# stm32f4-discovery-breakout-v2.net
KiCad netlist of a schematic drawn in EAGLE
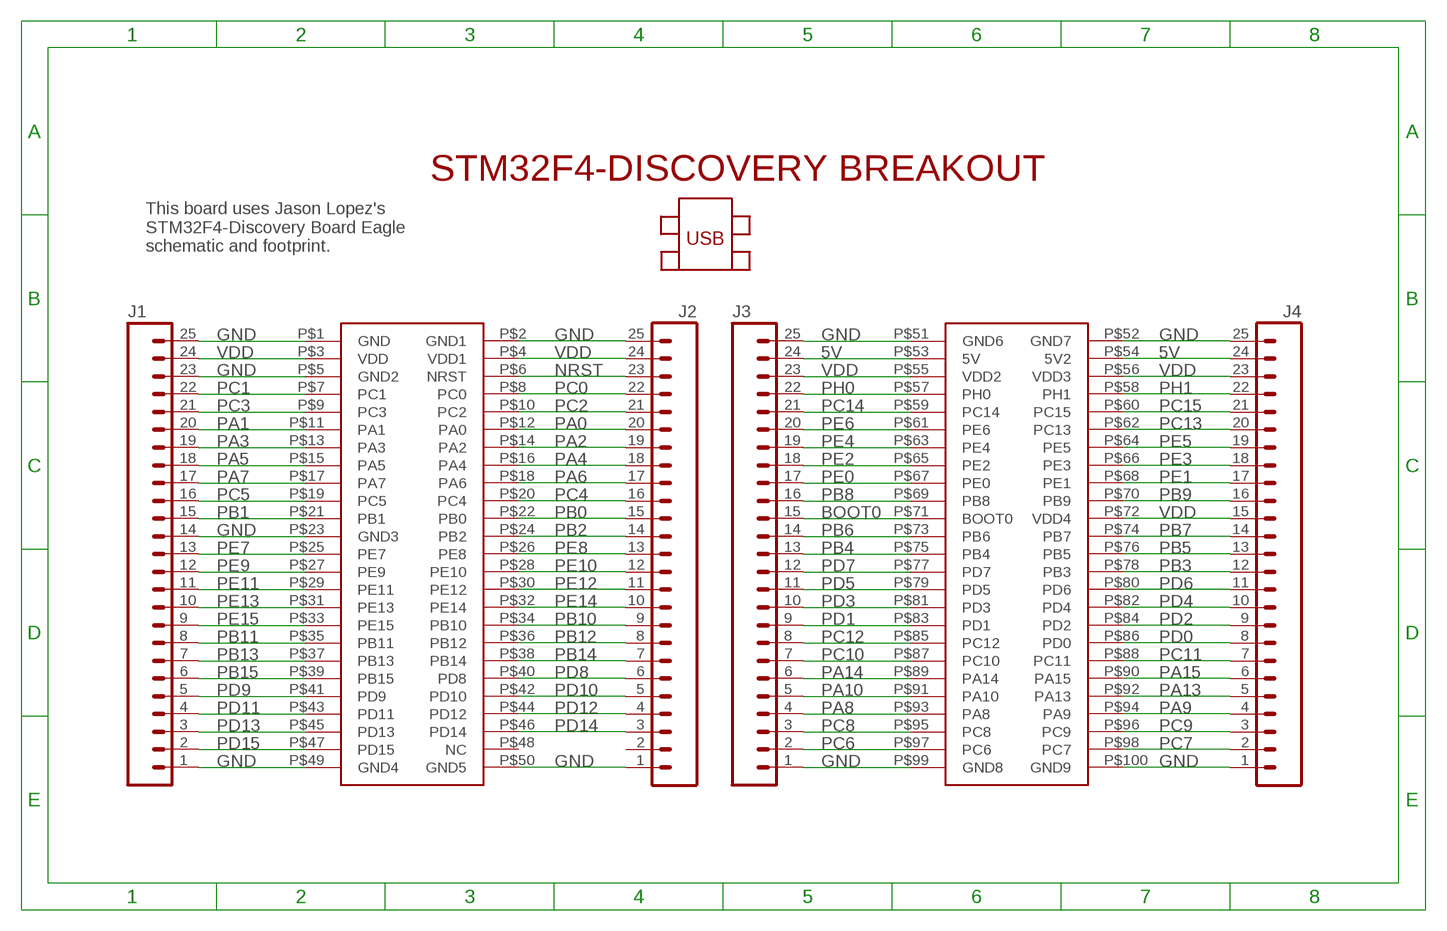
[diagram p0: schematic, sheet 1]

(export (version "E")
  (design (tool "Eeschema 10.0.6"))
  (components
    (comp (ref "J1")
      (value "M25LOCK_LONGPADS")
      (footprint "eagle-import:1X25_LOCK_LONGPADS")
      (libsource (lib "eagle-import") (part "M25LOCK_LONGPADS"))
    )
    (comp (ref "J2")
      (value "M25LOCK_LONGPADS")
      (footprint "eagle-import:1X25_LOCK_LONGPADS")
      (libsource (lib "eagle-import") (part "M25LOCK_LONGPADS"))
    )
    (comp (ref "J3")
      (value "M25LOCK_LONGPADS")
      (footprint "eagle-import:1X25_LOCK_LONGPADS")
      (libsource (lib "eagle-import") (part "M25LOCK_LONGPADS"))
    )
    (comp (ref "J4")
      (value "M25LOCK_LONGPADS")
      (footprint "eagle-import:1X25_LOCK_LONGPADS")
      (libsource (lib "eagle-import") (part "M25LOCK_LONGPADS"))
    )
    (comp (ref "U$1")
      (value "STM32F4-DISCOVERY")
      (footprint "eagle-import:STM32F4-DISCOVERY")
      (libsource (lib "eagle-import") (part "STM32F4-DISCOVERY"))
    )
  )
  (nets
    (net (code "1") (name "/5V") (class "Default")
      (node (ref "J3") (pin "24") (pinfunction "24_24") (pintype "passive"))
      (node (ref "J4") (pin "24") (pinfunction "24_24") (pintype "passive"))
      (node (ref "U$1") (pin "P$53") (pinfunction "5V_P$53") (pintype "bidirectional"))
      (node (ref "U$1") (pin "P$54") (pinfunction "5V2_P$54") (pintype "bidirectional"))
    )
    (net (code "2") (name "/BOOT0") (class "Default")
      (node (ref "J3") (pin "15") (pinfunction "15_15") (pintype "passive"))
      (node (ref "U$1") (pin "P$71") (pinfunction "BOOT0_P$71") (pintype "bidirectional"))
    )
    (net (code "3") (name "/GND") (class "Default")
      (node (ref "J1") (pin "1") (pinfunction "1_1") (pintype "passive"))
      (node (ref "J1") (pin "14") (pinfunction "14_14") (pintype "passive"))
      (node (ref "J1") (pin "23") (pinfunction "23_23") (pintype "passive"))
      (node (ref "J1") (pin "25") (pinfunction "25_25") (pintype "passive"))
      (node (ref "J2") (pin "1") (pinfunction "1_1") (pintype "passive"))
      (node (ref "J2") (pin "25") (pinfunction "25_25") (pintype "passive"))
      (node (ref "J3") (pin "1") (pinfunction "1_1") (pintype "passive"))
      (node (ref "J3") (pin "25") (pinfunction "25_25") (pintype "passive"))
      (node (ref "J4") (pin "1") (pinfunction "1_1") (pintype "passive"))
      (node (ref "J4") (pin "25") (pinfunction "25_25") (pintype "passive"))
      (node (ref "U$1") (pin "P$1") (pinfunction "GND_P$1") (pintype "bidirectional"))
      (node (ref "U$1") (pin "P$100") (pinfunction "GND9_P$100") (pintype "bidirectional"))
      (node (ref "U$1") (pin "P$2") (pinfunction "GND1_P$2") (pintype "bidirectional"))
      (node (ref "U$1") (pin "P$23") (pinfunction "GND3_P$23") (pintype "bidirectional"))
      (node (ref "U$1") (pin "P$49") (pinfunction "GND4_P$49") (pintype "bidirectional"))
      (node (ref "U$1") (pin "P$5") (pinfunction "GND2_P$5") (pintype "bidirectional"))
      (node (ref "U$1") (pin "P$50") (pinfunction "GND5_P$50") (pintype "bidirectional"))
      (node (ref "U$1") (pin "P$51") (pinfunction "GND6_P$51") (pintype "bidirectional"))
      (node (ref "U$1") (pin "P$52") (pinfunction "GND7_P$52") (pintype "bidirectional"))
      (node (ref "U$1") (pin "P$99") (pinfunction "GND8_P$99") (pintype "bidirectional"))
    )
    (net (code "4") (name "/NRST") (class "Default")
      (node (ref "J2") (pin "23") (pinfunction "23_23") (pintype "passive"))
      (node (ref "U$1") (pin "P$6") (pinfunction "NRST_P$6") (pintype "bidirectional"))
    )
    (net (code "5") (name "/PA0") (class "Default")
      (node (ref "J2") (pin "20") (pinfunction "20_20") (pintype "passive"))
      (node (ref "U$1") (pin "P$12") (pinfunction "PA0_P$12") (pintype "bidirectional"))
    )
    (net (code "6") (name "/PA1") (class "Default")
      (node (ref "J1") (pin "20") (pinfunction "20_20") (pintype "passive"))
      (node (ref "U$1") (pin "P$11") (pinfunction "PA1_P$11") (pintype "bidirectional"))
    )
    (net (code "7") (name "/PA2") (class "Default")
      (node (ref "J2") (pin "19") (pinfunction "19_19") (pintype "passive"))
      (node (ref "U$1") (pin "P$14") (pinfunction "PA2_P$14") (pintype "bidirectional"))
    )
    (net (code "8") (name "/PA3") (class "Default")
      (node (ref "J1") (pin "19") (pinfunction "19_19") (pintype "passive"))
      (node (ref "U$1") (pin "P$13") (pinfunction "PA3_P$13") (pintype "bidirectional"))
    )
    (net (code "9") (name "/PA4") (class "Default")
      (node (ref "J2") (pin "18") (pinfunction "18_18") (pintype "passive"))
      (node (ref "U$1") (pin "P$16") (pinfunction "PA4_P$16") (pintype "bidirectional"))
    )
    (net (code "10") (name "/PA5") (class "Default")
      (node (ref "J1") (pin "18") (pinfunction "18_18") (pintype "passive"))
      (node (ref "U$1") (pin "P$15") (pinfunction "PA5_P$15") (pintype "bidirectional"))
    )
    (net (code "11") (name "/PA6") (class "Default")
      (node (ref "J2") (pin "17") (pinfunction "17_17") (pintype "passive"))
      (node (ref "U$1") (pin "P$18") (pinfunction "PA6_P$18") (pintype "bidirectional"))
    )
    (net (code "12") (name "/PA7") (class "Default")
      (node (ref "J1") (pin "17") (pinfunction "17_17") (pintype "passive"))
      (node (ref "U$1") (pin "P$17") (pinfunction "PA7_P$17") (pintype "bidirectional"))
    )
    (net (code "13") (name "/PA8") (class "Default")
      (node (ref "J3") (pin "4") (pinfunction "4_4") (pintype "passive"))
      (node (ref "U$1") (pin "P$93") (pinfunction "PA8_P$93") (pintype "bidirectional"))
    )
    (net (code "14") (name "/PA9") (class "Default")
      (node (ref "J4") (pin "4") (pinfunction "4_4") (pintype "passive"))
      (node (ref "U$1") (pin "P$94") (pinfunction "PA9_P$94") (pintype "bidirectional"))
    )
    (net (code "15") (name "/PA10") (class "Default")
      (node (ref "J3") (pin "5") (pinfunction "5_5") (pintype "passive"))
      (node (ref "U$1") (pin "P$91") (pinfunction "PA10_P$91") (pintype "bidirectional"))
    )
    (net (code "16") (name "/PA13") (class "Default")
      (node (ref "J4") (pin "5") (pinfunction "5_5") (pintype "passive"))
      (node (ref "U$1") (pin "P$92") (pinfunction "PA13_P$92") (pintype "bidirectional"))
    )
    (net (code "17") (name "/PA14") (class "Default")
      (node (ref "J3") (pin "6") (pinfunction "6_6") (pintype "passive"))
      (node (ref "U$1") (pin "P$89") (pinfunction "PA14_P$89") (pintype "bidirectional"))
    )
    (net (code "18") (name "/PA15") (class "Default")
      (node (ref "J4") (pin "6") (pinfunction "6_6") (pintype "passive"))
      (node (ref "U$1") (pin "P$90") (pinfunction "PA15_P$90") (pintype "bidirectional"))
    )
    (net (code "19") (name "/PB0") (class "Default")
      (node (ref "J2") (pin "15") (pinfunction "15_15") (pintype "passive"))
      (node (ref "U$1") (pin "P$22") (pinfunction "PB0_P$22") (pintype "bidirectional"))
    )
    (net (code "20") (name "/PB1") (class "Default")
      (node (ref "J1") (pin "15") (pinfunction "15_15") (pintype "passive"))
      (node (ref "U$1") (pin "P$21") (pinfunction "PB1_P$21") (pintype "bidirectional"))
    )
    (net (code "21") (name "/PB2") (class "Default")
      (node (ref "J2") (pin "14") (pinfunction "14_14") (pintype "passive"))
      (node (ref "U$1") (pin "P$24") (pinfunction "PB2_P$24") (pintype "bidirectional"))
    )
    (net (code "22") (name "/PB3") (class "Default")
      (node (ref "J4") (pin "12") (pinfunction "12_12") (pintype "passive"))
      (node (ref "U$1") (pin "P$78") (pinfunction "PB3_P$78") (pintype "bidirectional"))
    )
    (net (code "23") (name "/PB4") (class "Default")
      (node (ref "J3") (pin "13") (pinfunction "13_13") (pintype "passive"))
      (node (ref "U$1") (pin "P$75") (pinfunction "PB4_P$75") (pintype "bidirectional"))
    )
    (net (code "24") (name "/PB5") (class "Default")
      (node (ref "J4") (pin "13") (pinfunction "13_13") (pintype "passive"))
      (node (ref "U$1") (pin "P$76") (pinfunction "PB5_P$76") (pintype "bidirectional"))
    )
    (net (code "25") (name "/PB6") (class "Default")
      (node (ref "J3") (pin "14") (pinfunction "14_14") (pintype "passive"))
      (node (ref "U$1") (pin "P$73") (pinfunction "PB6_P$73") (pintype "bidirectional"))
    )
    (net (code "26") (name "/PB7") (class "Default")
      (node (ref "J4") (pin "14") (pinfunction "14_14") (pintype "passive"))
      (node (ref "U$1") (pin "P$74") (pinfunction "PB7_P$74") (pintype "bidirectional"))
    )
    (net (code "27") (name "/PB8") (class "Default")
      (node (ref "J3") (pin "16") (pinfunction "16_16") (pintype "passive"))
      (node (ref "U$1") (pin "P$69") (pinfunction "PB8_P$69") (pintype "bidirectional"))
    )
    (net (code "28") (name "/PB9") (class "Default")
      (node (ref "J4") (pin "16") (pinfunction "16_16") (pintype "passive"))
      (node (ref "U$1") (pin "P$70") (pinfunction "PB9_P$70") (pintype "bidirectional"))
    )
    (net (code "29") (name "/PB10") (class "Default")
      (node (ref "J2") (pin "9") (pinfunction "9_9") (pintype "passive"))
      (node (ref "U$1") (pin "P$34") (pinfunction "PB10_P$34") (pintype "bidirectional"))
    )
    (net (code "30") (name "/PB11") (class "Default")
      (node (ref "J1") (pin "8") (pinfunction "8_8") (pintype "passive"))
      (node (ref "U$1") (pin "P$35") (pinfunction "PB11_P$35") (pintype "bidirectional"))
    )
    (net (code "31") (name "/PB12") (class "Default")
      (node (ref "J2") (pin "8") (pinfunction "8_8") (pintype "passive"))
      (node (ref "U$1") (pin "P$36") (pinfunction "PB12_P$36") (pintype "bidirectional"))
    )
    (net (code "32") (name "/PB13") (class "Default")
      (node (ref "J1") (pin "7") (pinfunction "7_7") (pintype "passive"))
      (node (ref "U$1") (pin "P$37") (pinfunction "PB13_P$37") (pintype "bidirectional"))
    )
    (net (code "33") (name "/PB14") (class "Default")
      (node (ref "J2") (pin "7") (pinfunction "7_7") (pintype "passive"))
      (node (ref "U$1") (pin "P$38") (pinfunction "PB14_P$38") (pintype "bidirectional"))
    )
    (net (code "34") (name "/PB15") (class "Default")
      (node (ref "J1") (pin "6") (pinfunction "6_6") (pintype "passive"))
      (node (ref "U$1") (pin "P$39") (pinfunction "PB15_P$39") (pintype "bidirectional"))
    )
    (net (code "35") (name "/PC0") (class "Default")
      (node (ref "J2") (pin "22") (pinfunction "22_22") (pintype "passive"))
      (node (ref "U$1") (pin "P$8") (pinfunction "PC0_P$8") (pintype "bidirectional"))
    )
    (net (code "36") (name "/PC1") (class "Default")
      (node (ref "J1") (pin "22") (pinfunction "22_22") (pintype "passive"))
      (node (ref "U$1") (pin "P$7") (pinfunction "PC1_P$7") (pintype "bidirectional"))
    )
    (net (code "37") (name "/PC2") (class "Default")
      (node (ref "J2") (pin "21") (pinfunction "21_21") (pintype "passive"))
      (node (ref "U$1") (pin "P$10") (pinfunction "PC2_P$10") (pintype "bidirectional"))
    )
    (net (code "38") (name "/PC3") (class "Default")
      (node (ref "J1") (pin "21") (pinfunction "21_21") (pintype "passive"))
      (node (ref "U$1") (pin "P$9") (pinfunction "PC3_P$9") (pintype "bidirectional"))
    )
    (net (code "39") (name "/PC4") (class "Default")
      (node (ref "J2") (pin "16") (pinfunction "16_16") (pintype "passive"))
      (node (ref "U$1") (pin "P$20") (pinfunction "PC4_P$20") (pintype "bidirectional"))
    )
    (net (code "40") (name "/PC5") (class "Default")
      (node (ref "J1") (pin "16") (pinfunction "16_16") (pintype "passive"))
      (node (ref "U$1") (pin "P$19") (pinfunction "PC5_P$19") (pintype "bidirectional"))
    )
    (net (code "41") (name "/PC6") (class "Default")
      (node (ref "J3") (pin "2") (pinfunction "2_2") (pintype "passive"))
      (node (ref "U$1") (pin "P$97") (pinfunction "PC6_P$97") (pintype "bidirectional"))
    )
    (net (code "42") (name "/PC7") (class "Default")
      (node (ref "J4") (pin "2") (pinfunction "2_2") (pintype "passive"))
      (node (ref "U$1") (pin "P$98") (pinfunction "PC7_P$98") (pintype "bidirectional"))
    )
    (net (code "43") (name "/PC8") (class "Default")
      (node (ref "J3") (pin "3") (pinfunction "3_3") (pintype "passive"))
      (node (ref "U$1") (pin "P$95") (pinfunction "PC8_P$95") (pintype "bidirectional"))
    )
    (net (code "44") (name "/PC9") (class "Default")
      (node (ref "J4") (pin "3") (pinfunction "3_3") (pintype "passive"))
      (node (ref "U$1") (pin "P$96") (pinfunction "PC9_P$96") (pintype "bidirectional"))
    )
    (net (code "45") (name "/PC10") (class "Default")
      (node (ref "J3") (pin "7") (pinfunction "7_7") (pintype "passive"))
      (node (ref "U$1") (pin "P$87") (pinfunction "PC10_P$87") (pintype "bidirectional"))
    )
    (net (code "46") (name "/PC11") (class "Default")
      (node (ref "J4") (pin "7") (pinfunction "7_7") (pintype "passive"))
      (node (ref "U$1") (pin "P$88") (pinfunction "PC11_P$88") (pintype "bidirectional"))
    )
    (net (code "47") (name "/PC12") (class "Default")
      (node (ref "J3") (pin "8") (pinfunction "8_8") (pintype "passive"))
      (node (ref "U$1") (pin "P$85") (pinfunction "PC12_P$85") (pintype "bidirectional"))
    )
    (net (code "48") (name "/PC13") (class "Default")
      (node (ref "J4") (pin "20") (pinfunction "20_20") (pintype "passive"))
      (node (ref "U$1") (pin "P$62") (pinfunction "PC13_P$62") (pintype "bidirectional"))
    )
    (net (code "49") (name "/PC14") (class "Default")
      (node (ref "J3") (pin "21") (pinfunction "21_21") (pintype "passive"))
      (node (ref "U$1") (pin "P$59") (pinfunction "PC14_P$59") (pintype "bidirectional"))
    )
    (net (code "50") (name "/PC15") (class "Default")
      (node (ref "J4") (pin "21") (pinfunction "21_21") (pintype "passive"))
      (node (ref "U$1") (pin "P$60") (pinfunction "PC15_P$60") (pintype "bidirectional"))
    )
    (net (code "51") (name "/PD0") (class "Default")
      (node (ref "J4") (pin "8") (pinfunction "8_8") (pintype "passive"))
      (node (ref "U$1") (pin "P$86") (pinfunction "PD0_P$86") (pintype "bidirectional"))
    )
    (net (code "52") (name "/PD1") (class "Default")
      (node (ref "J3") (pin "9") (pinfunction "9_9") (pintype "passive"))
      (node (ref "U$1") (pin "P$83") (pinfunction "PD1_P$83") (pintype "bidirectional"))
    )
    (net (code "53") (name "/PD2") (class "Default")
      (node (ref "J4") (pin "9") (pinfunction "9_9") (pintype "passive"))
      (node (ref "U$1") (pin "P$84") (pinfunction "PD2_P$84") (pintype "bidirectional"))
    )
    (net (code "54") (name "/PD3") (class "Default")
      (node (ref "J3") (pin "10") (pinfunction "10_10") (pintype "passive"))
      (node (ref "U$1") (pin "P$81") (pinfunction "PD3_P$81") (pintype "bidirectional"))
    )
    (net (code "55") (name "/PD4") (class "Default")
      (node (ref "J4") (pin "10") (pinfunction "10_10") (pintype "passive"))
      (node (ref "U$1") (pin "P$82") (pinfunction "PD4_P$82") (pintype "bidirectional"))
    )
    (net (code "56") (name "/PD5") (class "Default")
      (node (ref "J3") (pin "11") (pinfunction "11_11") (pintype "passive"))
      (node (ref "U$1") (pin "P$79") (pinfunction "PD5_P$79") (pintype "bidirectional"))
    )
    (net (code "57") (name "/PD6") (class "Default")
      (node (ref "J4") (pin "11") (pinfunction "11_11") (pintype "passive"))
      (node (ref "U$1") (pin "P$80") (pinfunction "PD6_P$80") (pintype "bidirectional"))
    )
    (net (code "58") (name "/PD7") (class "Default")
      (node (ref "J3") (pin "12") (pinfunction "12_12") (pintype "passive"))
      (node (ref "U$1") (pin "P$77") (pinfunction "PD7_P$77") (pintype "bidirectional"))
    )
    (net (code "59") (name "/PD8") (class "Default")
      (node (ref "J2") (pin "6") (pinfunction "6_6") (pintype "passive"))
      (node (ref "U$1") (pin "P$40") (pinfunction "PD8_P$40") (pintype "bidirectional"))
    )
    (net (code "60") (name "/PD9") (class "Default")
      (node (ref "J1") (pin "5") (pinfunction "5_5") (pintype "passive"))
      (node (ref "U$1") (pin "P$41") (pinfunction "PD9_P$41") (pintype "bidirectional"))
    )
    (net (code "61") (name "/PD10") (class "Default")
      (node (ref "J2") (pin "5") (pinfunction "5_5") (pintype "passive"))
      (node (ref "U$1") (pin "P$42") (pinfunction "PD10_P$42") (pintype "bidirectional"))
    )
    (net (code "62") (name "/PD11") (class "Default")
      (node (ref "J1") (pin "4") (pinfunction "4_4") (pintype "passive"))
      (node (ref "U$1") (pin "P$43") (pinfunction "PD11_P$43") (pintype "bidirectional"))
    )
    (net (code "63") (name "/PD12") (class "Default")
      (node (ref "J2") (pin "4") (pinfunction "4_4") (pintype "passive"))
      (node (ref "U$1") (pin "P$44") (pinfunction "PD12_P$44") (pintype "bidirectional"))
    )
    (net (code "64") (name "/PD13") (class "Default")
      (node (ref "J1") (pin "3") (pinfunction "3_3") (pintype "passive"))
      (node (ref "U$1") (pin "P$45") (pinfunction "PD13_P$45") (pintype "bidirectional"))
    )
    (net (code "65") (name "/PD14") (class "Default")
      (node (ref "J2") (pin "3") (pinfunction "3_3") (pintype "passive"))
      (node (ref "U$1") (pin "P$46") (pinfunction "PD14_P$46") (pintype "bidirectional"))
    )
    (net (code "66") (name "/PD15") (class "Default")
      (node (ref "J1") (pin "2") (pinfunction "2_2") (pintype "passive"))
      (node (ref "U$1") (pin "P$47") (pinfunction "PD15_P$47") (pintype "bidirectional"))
    )
    (net (code "67") (name "/PE0") (class "Default")
      (node (ref "J3") (pin "17") (pinfunction "17_17") (pintype "passive"))
      (node (ref "U$1") (pin "P$67") (pinfunction "PE0_P$67") (pintype "bidirectional"))
    )
    (net (code "68") (name "/PE1") (class "Default")
      (node (ref "J4") (pin "17") (pinfunction "17_17") (pintype "passive"))
      (node (ref "U$1") (pin "P$68") (pinfunction "PE1_P$68") (pintype "bidirectional"))
    )
    (net (code "69") (name "/PE2") (class "Default")
      (node (ref "J3") (pin "18") (pinfunction "18_18") (pintype "passive"))
      (node (ref "U$1") (pin "P$65") (pinfunction "PE2_P$65") (pintype "bidirectional"))
    )
    (net (code "70") (name "/PE3") (class "Default")
      (node (ref "J4") (pin "18") (pinfunction "18_18") (pintype "passive"))
      (node (ref "U$1") (pin "P$66") (pinfunction "PE3_P$66") (pintype "bidirectional"))
    )
    (net (code "71") (name "/PE4") (class "Default")
      (node (ref "J3") (pin "19") (pinfunction "19_19") (pintype "passive"))
      (node (ref "U$1") (pin "P$63") (pinfunction "PE4_P$63") (pintype "bidirectional"))
    )
    (net (code "72") (name "/PE5") (class "Default")
      (node (ref "J4") (pin "19") (pinfunction "19_19") (pintype "passive"))
      (node (ref "U$1") (pin "P$64") (pinfunction "PE5_P$64") (pintype "bidirectional"))
    )
    (net (code "73") (name "/PE6") (class "Default")
      (node (ref "J3") (pin "20") (pinfunction "20_20") (pintype "passive"))
      (node (ref "U$1") (pin "P$61") (pinfunction "PE6_P$61") (pintype "bidirectional"))
    )
    (net (code "74") (name "/PE7") (class "Default")
      (node (ref "J1") (pin "13") (pinfunction "13_13") (pintype "passive"))
      (node (ref "U$1") (pin "P$25") (pinfunction "PE7_P$25") (pintype "bidirectional"))
    )
    (net (code "75") (name "/PE8") (class "Default")
      (node (ref "J2") (pin "13") (pinfunction "13_13") (pintype "passive"))
      (node (ref "U$1") (pin "P$26") (pinfunction "PE8_P$26") (pintype "bidirectional"))
    )
    (net (code "76") (name "/PE9") (class "Default")
      (node (ref "J1") (pin "12") (pinfunction "12_12") (pintype "passive"))
      (node (ref "U$1") (pin "P$27") (pinfunction "PE9_P$27") (pintype "bidirectional"))
    )
    (net (code "77") (name "/PE10") (class "Default")
      (node (ref "J2") (pin "12") (pinfunction "12_12") (pintype "passive"))
      (node (ref "U$1") (pin "P$28") (pinfunction "PE10_P$28") (pintype "bidirectional"))
    )
    (net (code "78") (name "/PE11") (class "Default")
      (node (ref "J1") (pin "11") (pinfunction "11_11") (pintype "passive"))
      (node (ref "U$1") (pin "P$29") (pinfunction "PE11_P$29") (pintype "bidirectional"))
    )
    (net (code "79") (name "/PE12") (class "Default")
      (node (ref "J2") (pin "11") (pinfunction "11_11") (pintype "passive"))
      (node (ref "U$1") (pin "P$30") (pinfunction "PE12_P$30") (pintype "bidirectional"))
    )
    (net (code "80") (name "/PE13") (class "Default")
      (node (ref "J1") (pin "10") (pinfunction "10_10") (pintype "passive"))
      (node (ref "U$1") (pin "P$31") (pinfunction "PE13_P$31") (pintype "bidirectional"))
    )
    (net (code "81") (name "/PE14") (class "Default")
      (node (ref "J2") (pin "10") (pinfunction "10_10") (pintype "passive"))
      (node (ref "U$1") (pin "P$32") (pinfunction "PE14_P$32") (pintype "bidirectional"))
    )
    (net (code "82") (name "/PE15") (class "Default")
      (node (ref "J1") (pin "9") (pinfunction "9_9") (pintype "passive"))
      (node (ref "U$1") (pin "P$33") (pinfunction "PE15_P$33") (pintype "bidirectional"))
    )
    (net (code "83") (name "/PH0") (class "Default")
      (node (ref "J3") (pin "22") (pinfunction "22_22") (pintype "passive"))
      (node (ref "U$1") (pin "P$57") (pinfunction "PH0_P$57") (pintype "bidirectional"))
    )
    (net (code "84") (name "/PH1") (class "Default")
      (node (ref "J4") (pin "22") (pinfunction "22_22") (pintype "passive"))
      (node (ref "U$1") (pin "P$58") (pinfunction "PH1_P$58") (pintype "bidirectional"))
    )
    (net (code "85") (name "/VDD") (class "Default")
      (node (ref "J1") (pin "24") (pinfunction "24_24") (pintype "passive"))
      (node (ref "J2") (pin "24") (pinfunction "24_24") (pintype "passive"))
      (node (ref "J3") (pin "23") (pinfunction "23_23") (pintype "passive"))
      (node (ref "J4") (pin "15") (pinfunction "15_15") (pintype "passive"))
      (node (ref "J4") (pin "23") (pinfunction "23_23") (pintype "passive"))
      (node (ref "U$1") (pin "P$3") (pinfunction "VDD_P$3") (pintype "bidirectional"))
      (node (ref "U$1") (pin "P$4") (pinfunction "VDD1_P$4") (pintype "bidirectional"))
      (node (ref "U$1") (pin "P$55") (pinfunction "VDD2_P$55") (pintype "bidirectional"))
      (node (ref "U$1") (pin "P$56") (pinfunction "VDD3_P$56") (pintype "bidirectional"))
      (node (ref "U$1") (pin "P$72") (pinfunction "VDD4_P$72") (pintype "bidirectional"))
    )
    (net (code "86") (name "unconnected-(J2-Pad2)") (class "Default")
      (node (ref "J2") (pin "2") (pinfunction "2_2") (pintype "passive"))
    )
    (net (code "87") (name "unconnected-(U$1-NC-PadP$48)") (class "Default")
      (node (ref "U$1") (pin "P$48") (pinfunction "NC_P$48") (pintype "bidirectional"))
    )
  )
)
